# Serial.net
KiCad netlist of a schematic drawn in Altium Designer
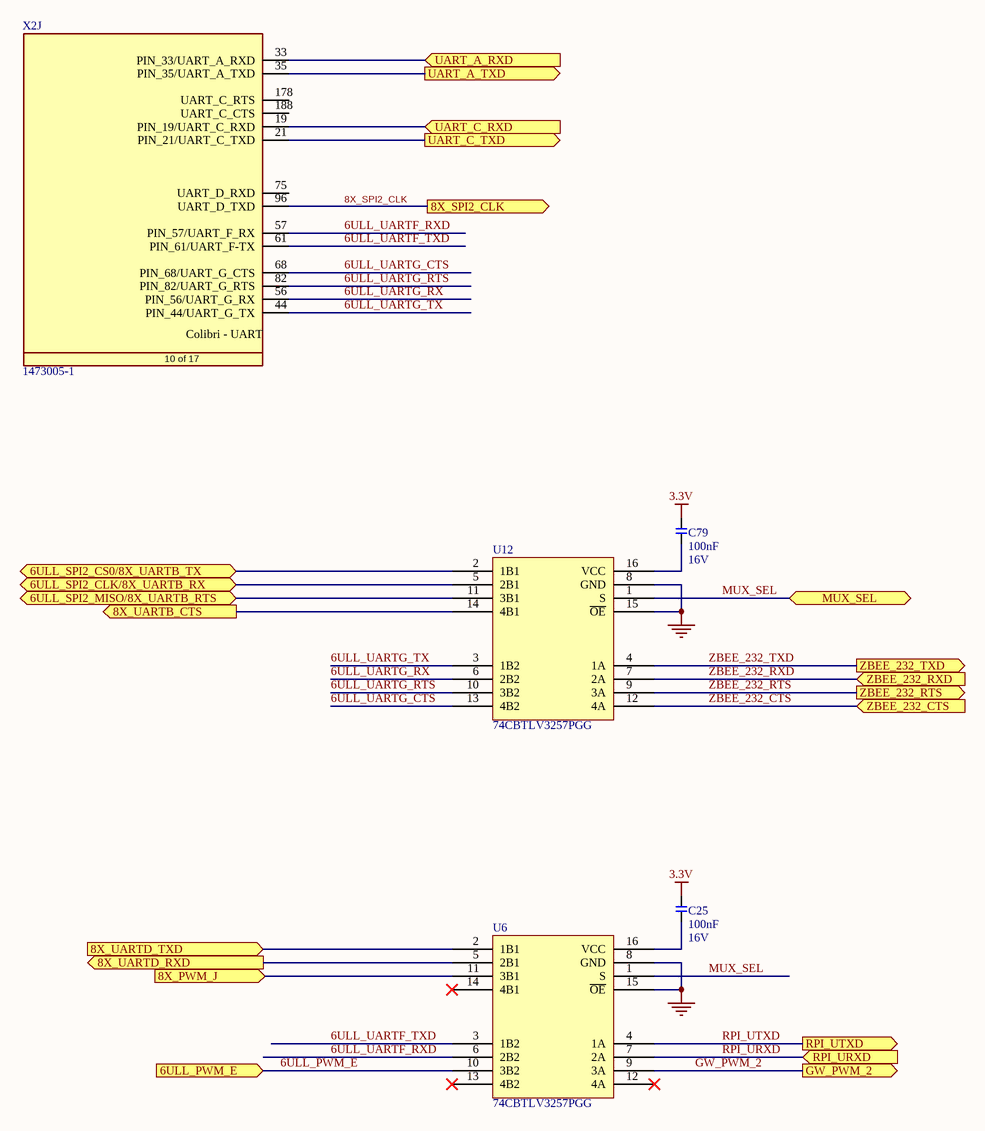
[diagram p0: Serial.SchDoc]

(export (version "E")
  (design (tool "Eeschema 10.0.6"))
  (components
    (comp (ref "C25")
      (value "100nF")
      (footprint "T_CAPC0603X33N")
      (description "Capacitor Ceramic X7R 100nF 16V 10% 0603")
      (fields (field (name "TOLERANCE") "10%") (field (name "RATING") "16V"))
      (libsource (lib "Iris") (part "C-X7R-100nF-16V-10%-0603"))
    )
    (comp (ref "C79")
      (value "100nF")
      (footprint "T_CAPC0603X33N")
      (description "Capacitor Ceramic X7R 100nF 16V 10% 0603")
      (fields (field (name "TOLERANCE") "10%") (field (name "RATING") "16V"))
      (libsource (lib "Iris") (part "C-X7R-100nF-16V-10%-0603"))
    )
    (comp (ref "U6")
      (value "74CBTLV3257PGG")
      (footprint "SOP65P640X120-16N")
      (libsource (lib "Inlib") (part "74CBTLV3257PGG"))
    )
    (comp (ref "U12")
      (value "74CBTLV3257PGG")
      (footprint "SOP65P640X120-16N")
      (libsource (lib "Inlib") (part "74CBTLV3257PGG"))
    )
    (comp (ref "X2")
      (value "1473005-1")
      (footprint "T_Tyco_1473005-1")
      (description "SODIMM Connector")
      (fields (field (name "MANUFACTURER PART NO.") "1473005-1"))
      (libsource (lib "Iris") (part "CON-Tyco-1473005-1-200-0.6mm"))
    )
  )
  (nets
    (net (code "1") (name "/6ULL_PWM_E") (class "Default")
      (node (ref "U6") (pin "10") (pinfunction "3B2_10") (pintype "passive"))
    )
    (net (code "2") (name "/6ULL_SPI2_CLK{slash}8X_UARTB_RX") (class "Default")
      (node (ref "U12") (pin "5") (pinfunction "2B1_5") (pintype "passive"))
    )
    (net (code "3") (name "/6ULL_SPI2_CS0{slash}8X_UARTB_TX") (class "Default")
      (node (ref "U12") (pin "2") (pinfunction "1B1_2") (pintype "passive"))
    )
    (net (code "4") (name "/6ULL_SPI2_MISO{slash}8X_UARTB_RTS") (class "Default")
      (node (ref "U12") (pin "11") (pinfunction "3B1_11") (pintype "passive"))
    )
    (net (code "5") (name "/6ULL_UARTF_RXD") (class "Default")
      (node (ref "U6") (pin "6") (pinfunction "2B2_6") (pintype "passive"))
      (node (ref "X2") (pin "57") (pinfunction "PIN_57/UART_F_RX_57") (pintype "passive"))
    )
    (net (code "6") (name "/6ULL_UARTF_TXD") (class "Default")
      (node (ref "U6") (pin "3") (pinfunction "1B2_3") (pintype "passive"))
      (node (ref "X2") (pin "61") (pinfunction "PIN_61/UART_F-TX_61") (pintype "passive"))
    )
    (net (code "7") (name "/6ULL_UARTG_CTS") (class "Default")
      (node (ref "U12") (pin "13") (pinfunction "4B2_13") (pintype "passive"))
      (node (ref "X2") (pin "68") (pinfunction "PIN_68/UART_G_CTS_68") (pintype "passive"))
    )
    (net (code "8") (name "/6ULL_UARTG_RTS") (class "Default")
      (node (ref "U12") (pin "10") (pinfunction "3B2_10") (pintype "passive"))
      (node (ref "X2") (pin "82") (pinfunction "PIN_82/UART_G_RTS_82") (pintype "passive"))
    )
    (net (code "9") (name "/6ULL_UARTG_RX") (class "Default")
      (node (ref "U12") (pin "6") (pinfunction "2B2_6") (pintype "passive"))
      (node (ref "X2") (pin "56") (pinfunction "PIN_56/UART_G_RX_56") (pintype "passive"))
    )
    (net (code "10") (name "/6ULL_UARTG_TX") (class "Default")
      (node (ref "U12") (pin "3") (pinfunction "1B2_3") (pintype "passive"))
      (node (ref "X2") (pin "44") (pinfunction "PIN_44/UART_G_TX_44") (pintype "passive"))
    )
    (net (code "11") (name "/8X_PWM_J") (class "Default")
      (node (ref "U6") (pin "11") (pinfunction "3B1_11") (pintype "passive"))
    )
    (net (code "12") (name "/8X_SPI2_CLK") (class "Default")
      (node (ref "X2") (pin "96") (pinfunction "UART_D_TXD_96") (pintype "passive"))
    )
    (net (code "13") (name "/8X_UARTB_CTS") (class "Default")
      (node (ref "U12") (pin "14") (pinfunction "4B1_14") (pintype "passive"))
    )
    (net (code "14") (name "/8X_UARTD_RXD") (class "Default")
      (node (ref "U6") (pin "5") (pinfunction "2B1_5") (pintype "passive"))
    )
    (net (code "15") (name "/8X_UARTD_TXD") (class "Default")
      (node (ref "U6") (pin "2") (pinfunction "1B1_2") (pintype "passive"))
    )
    (net (code "16") (name "/GW_PWM_2") (class "Default")
      (node (ref "U6") (pin "9") (pinfunction "3A_9") (pintype "passive"))
    )
    (net (code "17") (name "/MUX_SEL") (class "Default")
      (node (ref "U12") (pin "1") (pinfunction "S_1") (pintype "passive"))
      (node (ref "U6") (pin "1") (pinfunction "S_1") (pintype "passive"))
    )
    (net (code "18") (name "/RPI_URXD") (class "Default")
      (node (ref "U6") (pin "7") (pinfunction "2A_7") (pintype "passive"))
    )
    (net (code "19") (name "/RPI_UTXD") (class "Default")
      (node (ref "U6") (pin "4") (pinfunction "1A_4") (pintype "passive"))
    )
    (net (code "20") (name "/UART_A_RXD") (class "Default")
      (node (ref "X2") (pin "33") (pinfunction "PIN_33/UART_A_RXD_33") (pintype "passive"))
    )
    (net (code "21") (name "/UART_A_TXD") (class "Default")
      (node (ref "X2") (pin "35") (pinfunction "PIN_35/UART_A_TXD_35") (pintype "passive"))
    )
    (net (code "22") (name "/UART_C_RXD") (class "Default")
      (node (ref "X2") (pin "19") (pinfunction "PIN_19/UART_C_RXD_19") (pintype "passive"))
    )
    (net (code "23") (name "/UART_C_TXD") (class "Default")
      (node (ref "X2") (pin "21") (pinfunction "PIN_21/UART_C_TXD_21") (pintype "passive"))
    )
    (net (code "24") (name "/ZBEE_232_CTS") (class "Default")
      (node (ref "U12") (pin "12") (pinfunction "4A_12") (pintype "passive"))
    )
    (net (code "25") (name "/ZBEE_232_RTS") (class "Default")
      (node (ref "U12") (pin "9") (pinfunction "3A_9") (pintype "passive"))
    )
    (net (code "26") (name "/ZBEE_232_RXD") (class "Default")
      (node (ref "U12") (pin "7") (pinfunction "2A_7") (pintype "passive"))
    )
    (net (code "27") (name "/ZBEE_232_TXD") (class "Default")
      (node (ref "U12") (pin "4") (pinfunction "1A_4") (pintype "passive"))
    )
    (net (code "28") (name "3.3V") (class "Default")
      (node (ref "C25") (pin "2") (pinfunction "2_2") (pintype "passive"))
      (node (ref "C79") (pin "2") (pinfunction "2_2") (pintype "passive"))
    )
    (net (code "29") (name "GND") (class "Default")
      (node (ref "U12") (pin "15") (pinfunction "~{OE}_15") (pintype "passive"))
      (node (ref "U12") (pin "8") (pinfunction "GND_8") (pintype "passive"))
      (node (ref "U6") (pin "15") (pinfunction "~{OE}_15") (pintype "passive"))
      (node (ref "U6") (pin "8") (pinfunction "GND_8") (pintype "passive"))
    )
    (net (code "30") (name "Net-(U6-VCC)") (class "Default")
      (node (ref "C25") (pin "1") (pinfunction "1_1") (pintype "passive"))
      (node (ref "U6") (pin "16") (pinfunction "VCC_16") (pintype "passive"))
    )
    (net (code "31") (name "Net-(U12-VCC)") (class "Default")
      (node (ref "C79") (pin "1") (pinfunction "1_1") (pintype "passive"))
      (node (ref "U12") (pin "16") (pinfunction "VCC_16") (pintype "passive"))
    )
    (net (code "32") (name "unconnected-(U6-4A-Pad12)") (class "Default")
      (node (ref "U6") (pin "12") (pinfunction "4A_12") (pintype "passive+no_connect"))
    )
    (net (code "33") (name "unconnected-(U6-4B1-Pad14)") (class "Default")
      (node (ref "U6") (pin "14") (pinfunction "4B1_14") (pintype "passive+no_connect"))
    )
    (net (code "34") (name "unconnected-(U6-4B2-Pad13)") (class "Default")
      (node (ref "U6") (pin "13") (pinfunction "4B2_13") (pintype "passive+no_connect"))
    )
    (net (code "35") (name "unconnected-(X2J-UART_C_CTS-Pad188)") (class "Default")
      (node (ref "X2") (pin "188") (pinfunction "UART_C_CTS_188") (pintype "passive"))
    )
    (net (code "36") (name "unconnected-(X2J-UART_C_RTS-Pad178)") (class "Default")
      (node (ref "X2") (pin "178") (pinfunction "UART_C_RTS_178") (pintype "passive"))
    )
    (net (code "37") (name "unconnected-(X2J-UART_D_RXD-Pad75)") (class "Default")
      (node (ref "X2") (pin "75") (pinfunction "UART_D_RXD_75") (pintype "passive"))
    )
  )
)
